# daughterboard.net
KiCad netlist of a schematic drawn in EAGLE
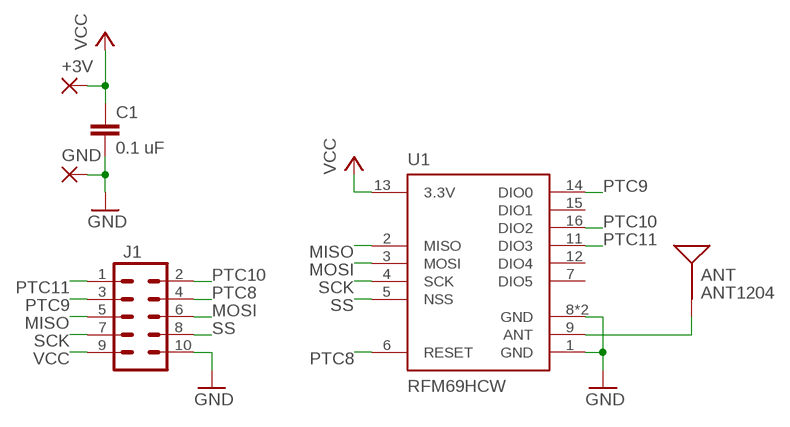
[diagram p0: schematic, sheet 1]

(export (version "E")
  (design (tool "Eeschema 10.0.6"))
  (components
    (comp (ref "+3V")
      (value "1,6/0,9")
      (footprint "eagle-import:1,6_0,9")
      (libsource (lib "eagle-import") (part "1,6/0,9"))
    )
    (comp (ref "ANT")
      (value "ANT1204")
      (footprint "eagle-import:ANT1204")
      (libsource (lib "eagle-import") (part "ANT1204"))
    )
    (comp (ref "C1")
      (value "0.1 uF")
      (footprint "eagle-import:C0603K")
      (libsource (lib "eagle-import") (part "C-EUC0603K"))
    )
    (comp (ref "GND")
      (value "1,6/0,9")
      (footprint "eagle-import:1,6_0,9")
      (libsource (lib "eagle-import") (part "1,6/0,9"))
    )
    (comp (ref "J1")
      (value "M05X2SHD_SMD")
      (footprint "eagle-import:2X5-SHROUDED_SMD")
      (libsource (lib "eagle-import") (part "M05X2SHD_SMD"))
    )
    (comp (ref "U1")
      (value "RFM69HCW")
      (footprint "eagle-import:RFM69HCW-XXXS2")
      (libsource (lib "eagle-import") (part "RFM69HCW"))
    )
  )
  (nets
    (net (code "1") (name "/MISO") (class "Default")
      (node (ref "J1") (pin "5") (pinfunction "5_5") (pintype "passive"))
      (node (ref "U1") (pin "2") (pinfunction "MISO_2") (pintype "bidirectional"))
    )
    (net (code "2") (name "/MOSI") (class "Default")
      (node (ref "J1") (pin "6") (pinfunction "6_6") (pintype "passive"))
      (node (ref "U1") (pin "3") (pinfunction "MOSI_3") (pintype "input"))
    )
    (net (code "3") (name "/PTC8") (class "Default")
      (node (ref "J1") (pin "4") (pinfunction "4_4") (pintype "passive"))
      (node (ref "U1") (pin "6") (pinfunction "RESET_6") (pintype "input"))
    )
    (net (code "4") (name "/PTC9") (class "Default")
      (node (ref "J1") (pin "3") (pinfunction "3_3") (pintype "passive"))
      (node (ref "U1") (pin "14") (pinfunction "DIO0_14") (pintype "bidirectional"))
    )
    (net (code "5") (name "/PTC10") (class "Default")
      (node (ref "J1") (pin "2") (pinfunction "2_2") (pintype "passive"))
      (node (ref "U1") (pin "16") (pinfunction "DIO2_16") (pintype "bidirectional"))
    )
    (net (code "6") (name "/PTC11") (class "Default")
      (node (ref "J1") (pin "1") (pinfunction "1_1") (pintype "passive"))
      (node (ref "U1") (pin "11") (pinfunction "DIO3_11") (pintype "bidirectional"))
    )
    (net (code "7") (name "/SCK") (class "Default")
      (node (ref "J1") (pin "7") (pinfunction "7_7") (pintype "passive"))
      (node (ref "U1") (pin "4") (pinfunction "SCK_4") (pintype "input"))
    )
    (net (code "8") (name "/SS") (class "Default")
      (node (ref "J1") (pin "8") (pinfunction "8_8") (pintype "passive"))
      (node (ref "U1") (pin "5") (pinfunction "NSS_5") (pintype "input"))
    )
    (net (code "9") (name "GND") (class "Default")
      (node (ref "C1") (pin "2") (pinfunction "2_2") (pintype "passive"))
      (node (ref "GND") (pin "1") (pinfunction "P_1") (pintype "passive"))
      (node (ref "J1") (pin "10") (pinfunction "10_10") (pintype "passive"))
      (node (ref "U1") (pin "1") (pinfunction "GND_1") (pintype "power_in"))
      (node (ref "U1") (pin "10") (pinfunction "GND_10") (pintype "power_in"))
      (node (ref "U1") (pin "8") (pinfunction "GND_8") (pintype "power_in"))
    )
    (net (code "10") (name "Net-(U1-ANT)") (class "Default")
      (node (ref "ANT") (pin "FEED") (pinfunction "FEED_FEED") (pintype "bidirectional"))
      (node (ref "U1") (pin "9") (pinfunction "ANT_9") (pintype "passive"))
    )
    (net (code "11") (name "VCC") (class "Default")
      (node (ref "+3V") (pin "1") (pinfunction "P_1") (pintype "passive"))
      (node (ref "C1") (pin "1") (pinfunction "1_1") (pintype "passive"))
      (node (ref "J1") (pin "9") (pinfunction "9_9") (pintype "passive"))
      (node (ref "U1") (pin "13") (pinfunction "3.3V_13") (pintype "power_in"))
    )
    (net (code "12") (name "unconnected-(U1-DIO1-Pad15)") (class "Default")
      (node (ref "U1") (pin "15") (pinfunction "DIO1_15") (pintype "bidirectional"))
    )
    (net (code "13") (name "unconnected-(U1-DIO4-Pad12)") (class "Default")
      (node (ref "U1") (pin "12") (pinfunction "DIO4_12") (pintype "bidirectional"))
    )
    (net (code "14") (name "unconnected-(U1-DIO5-Pad7)") (class "Default")
      (node (ref "U1") (pin "7") (pinfunction "DIO5_7") (pintype "bidirectional"))
    )
  )
)
